# cw312_xc7a35t_fpga_pwr.net
KiCad netlist of a schematic drawn in Altium Designer
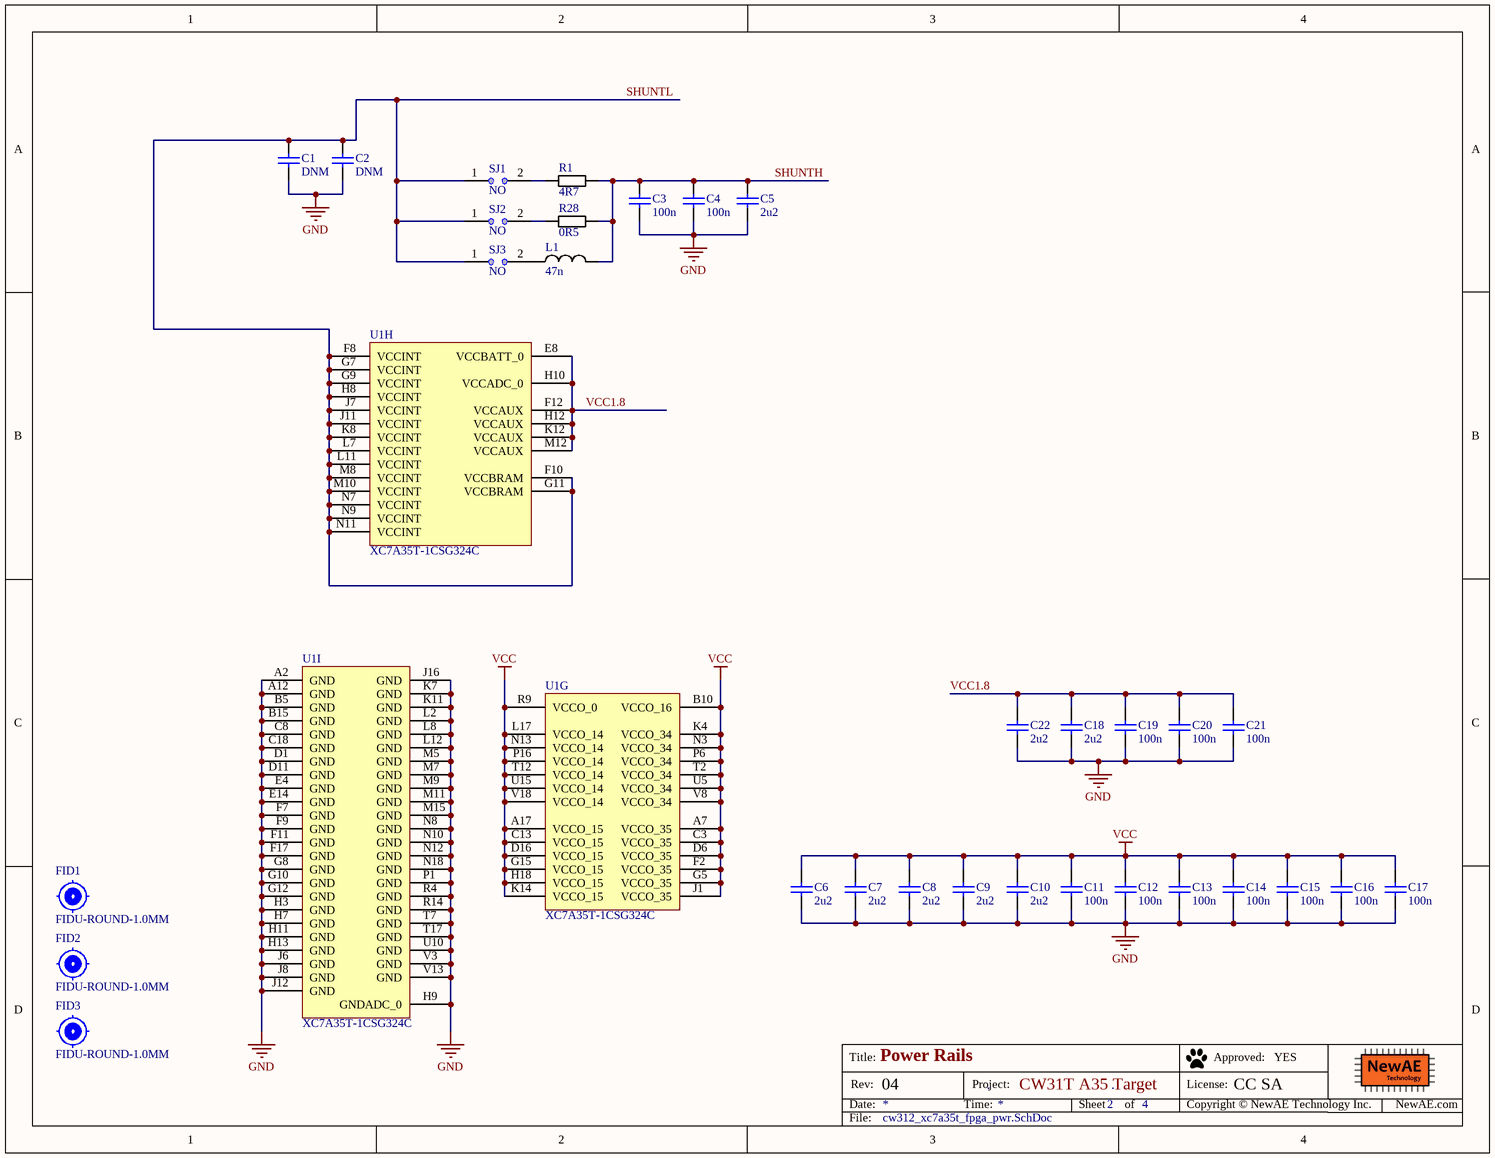
[diagram p0: cw312_xc7a35t_fpga_pwr.SchDoc]

(export (version "E")
  (design (tool "Eeschema 10.0.6"))
  (components
    (comp (ref "C1")
      (value "DNM")
      (footprint "CAPC0603_M")
      (fields (field (name "PART NUMBER") "CCHIP-100n-0603"))
      (libsource (lib "NewAE_AltiumLib") (part "CAP"))
    )
    (comp (ref "C2")
      (value "DNM")
      (footprint "CAPC0603_M")
      (fields (field (name "PART NUMBER") "CCHIP-100n-0603"))
      (libsource (lib "NewAE_AltiumLib") (part "CAP"))
    )
    (comp (ref "C3")
      (value "100n")
      (footprint "CAPC0603_M")
      (description "100n, 0603")
      (fields (field (name "PART NUMBER") "CCHIP-100n-0603"))
      (libsource (lib "NewAE_AltiumLib") (part "CAP"))
    )
    (comp (ref "C4")
      (value "100n")
      (footprint "CAPC0603_M")
      (description "100n, 0603")
      (fields (field (name "PART NUMBER") "CCHIP-100n-0603"))
      (libsource (lib "NewAE_AltiumLib") (part "CAP"))
    )
    (comp (ref "C5")
      (value "2u2")
      (footprint "CAPC0603_M")
      (description "2u2, 0603")
      (fields (field (name "PART NUMBER") "CCHIP-2u2-0603"))
      (libsource (lib "NewAE_AltiumLib") (part "CAP"))
    )
    (comp (ref "C6")
      (value "2u2")
      (footprint "CAPC0603_M")
      (description "2u2, 0603")
      (fields (field (name "PART NUMBER") "CCHIP-2u2-0603"))
      (libsource (lib "NewAE_AltiumLib") (part "CAP"))
    )
    (comp (ref "C7")
      (value "2u2")
      (footprint "CAPC0603_M")
      (description "2u2, 0603")
      (fields (field (name "PART NUMBER") "CCHIP-2u2-0603"))
      (libsource (lib "NewAE_AltiumLib") (part "CAP"))
    )
    (comp (ref "C8")
      (value "2u2")
      (footprint "CAPC0603_M")
      (description "2u2, 0603")
      (fields (field (name "PART NUMBER") "CCHIP-2u2-0603"))
      (libsource (lib "NewAE_AltiumLib") (part "CAP"))
    )
    (comp (ref "C9")
      (value "2u2")
      (footprint "CAPC0603_M")
      (description "2u2, 0603")
      (fields (field (name "PART NUMBER") "CCHIP-2u2-0603"))
      (libsource (lib "NewAE_AltiumLib") (part "CAP"))
    )
    (comp (ref "C10")
      (value "2u2")
      (footprint "CAPC0603_M")
      (description "2u2, 0603")
      (fields (field (name "PART NUMBER") "CCHIP-2u2-0603"))
      (libsource (lib "NewAE_AltiumLib") (part "CAP"))
    )
    (comp (ref "C11")
      (value "100n")
      (footprint "CAPC0402_M")
      (description "100n, 0402")
      (fields (field (name "PART NUMBER") "CCHIP-100n-0402"))
      (libsource (lib "NewAE_AltiumLib") (part "CAP"))
    )
    (comp (ref "C12")
      (value "100n")
      (footprint "CAPC0402_M")
      (description "100n, 0402")
      (fields (field (name "PART NUMBER") "CCHIP-100n-0402"))
      (libsource (lib "NewAE_AltiumLib") (part "CAP"))
    )
    (comp (ref "C13")
      (value "100n")
      (footprint "CAPC0402_M")
      (description "100n, 0402")
      (fields (field (name "PART NUMBER") "CCHIP-100n-0402"))
      (libsource (lib "NewAE_AltiumLib") (part "CAP"))
    )
    (comp (ref "C14")
      (value "100n")
      (footprint "CAPC0402_M")
      (description "100n, 0402")
      (fields (field (name "PART NUMBER") "CCHIP-100n-0402"))
      (libsource (lib "NewAE_AltiumLib") (part "CAP"))
    )
    (comp (ref "C15")
      (value "100n")
      (footprint "CAPC0402_M")
      (description "100n, 0402")
      (fields (field (name "PART NUMBER") "CCHIP-100n-0402"))
      (libsource (lib "NewAE_AltiumLib") (part "CAP"))
    )
    (comp (ref "C16")
      (value "100n")
      (footprint "CAPC0402_M")
      (description "100n, 0402")
      (fields (field (name "PART NUMBER") "CCHIP-100n-0402"))
      (libsource (lib "NewAE_AltiumLib") (part "CAP"))
    )
    (comp (ref "C17")
      (value "100n")
      (footprint "CAPC0402_M")
      (description "100n, 0402")
      (fields (field (name "PART NUMBER") "CCHIP-100n-0402"))
      (libsource (lib "NewAE_AltiumLib") (part "CAP"))
    )
    (comp (ref "C18")
      (value "2u2")
      (footprint "CAPC0603_M")
      (description "2u2, 0603")
      (fields (field (name "PART NUMBER") "CCHIP-2u2-0603"))
      (libsource (lib "NewAE_AltiumLib") (part "CAP"))
    )
    (comp (ref "C19")
      (value "100n")
      (footprint "CAPC0402_M")
      (description "100n, 0402")
      (fields (field (name "PART NUMBER") "CCHIP-100n-0402"))
      (libsource (lib "NewAE_AltiumLib") (part "CAP"))
    )
    (comp (ref "C20")
      (value "100n")
      (footprint "CAPC0402_M")
      (description "100n, 0402")
      (fields (field (name "PART NUMBER") "CCHIP-100n-0402"))
      (libsource (lib "NewAE_AltiumLib") (part "CAP"))
    )
    (comp (ref "C21")
      (value "100n")
      (footprint "CAPC0402_M")
      (description "100n, 0402")
      (fields (field (name "PART NUMBER") "CCHIP-100n-0402"))
      (libsource (lib "NewAE_AltiumLib") (part "CAP"))
    )
    (comp (ref "C22")
      (value "2u2")
      (footprint "CAPC0603_M")
      (description "2u2, 0603")
      (fields (field (name "PART NUMBER") "CCHIP-2u2-0603"))
      (libsource (lib "NewAE_AltiumLib") (part "CAP"))
    )
    (comp (ref "FID1")
      (value "FIDU-ROUND-1.0MM")
      (footprint "FIDU-ROUND-1.0mm")
      (description "ROUND FIDUCIAL")
      (libsource (lib "NewAE_AltiumLib") (part "FIDU-ROUND-1.0MM"))
    )
    (comp (ref "FID2")
      (value "FIDU-ROUND-1.0MM")
      (footprint "FIDU-ROUND-1.0mm")
      (description "ROUND FIDUCIAL")
      (libsource (lib "NewAE_AltiumLib") (part "FIDU-ROUND-1.0MM"))
    )
    (comp (ref "FID3")
      (value "FIDU-ROUND-1.0MM")
      (footprint "FIDU-ROUND-1.0mm")
      (description "ROUND FIDUCIAL")
      (libsource (lib "NewAE_AltiumLib") (part "FIDU-ROUND-1.0MM"))
    )
    (comp (ref "L1")
      (value "47n")
      (footprint "IND_0603")
      (description "FIXED IND 47NH 380MA 290 MOHM")
      (fields (field (name "PART NUMBER") "LCHIP-47N-0603") (field (name "TOLERANCE") "±5%"))
      (libsource (lib "NewAE_AltiumLib") (part "IND"))
    )
    (comp (ref "R1")
      (value "4R7")
      (footprint "RESC1608X55N")
      (description "4R7 res, 0603, 1%, 1/10W")
      (fields (field (name "PART NUMBER") "RCHIP-4R7-0603") (field (name "TOLERANCE") "1%"))
      (libsource (lib "NewAE_AltiumLib") (part "RES-EU"))
    )
    (comp (ref "R28")
      (value "0R5")
      (footprint "RESC1608X55N")
      (description "0R500 res, 0603, 1%, 1/10W")
      (fields (field (name "PART NUMBER") "RCHIP-0R500-0603") (field (name "TOLERANCE") "1%"))
      (libsource (lib "NewAE_AltiumLib") (part "RES-EU"))
    )
    (comp (ref "SJ1")
      (value "NO")
      (footprint "SJ_2S_NO")
      (description "Solder Jumper, NO")
      (fields (field (name "PART NUMBER") "SJ_2S_NO"))
      (libsource (lib "NewAE_AltiumLib") (part "SJ_2S_NO"))
    )
    (comp (ref "SJ2")
      (value "NO")
      (footprint "SJ_2S_NO")
      (description "Solder Jumper, NO")
      (fields (field (name "PART NUMBER") "SJ_2S_NO"))
      (libsource (lib "NewAE_AltiumLib") (part "SJ_2S_NO"))
    )
    (comp (ref "SJ3")
      (value "NO")
      (footprint "SJ_2S_NO")
      (description "Solder Jumper, NO")
      (fields (field (name "PART NUMBER") "SJ_2S_NO"))
      (libsource (lib "NewAE_AltiumLib") (part "SJ_2S_NO"))
    )
    (comp (ref "U1")
      (value "XC7A35T-1CSG324C")
      (footprint "CSG324")
      (description "Artix-7 FPGA, 210 User I/Os, 0 GTP, 324-Ball BGA, Speed Grade 1, Commercial Grade, Pb-Free")
      (fields (field (name "MANUFACTURER") "Xilinx"))
      (libsource (lib "Altium Content Vault") (part "XLNX-XC7A35T-CSG324"))
    )
  )
  (nets
    (net (code "1") (name "/SHUNTH") (class "Default")
      (node (ref "C3") (pin "1") (pinfunction "1_1") (pintype "passive"))
      (node (ref "C4") (pin "1") (pinfunction "1_1") (pintype "passive"))
      (node (ref "C5") (pin "1") (pinfunction "1_1") (pintype "passive"))
      (node (ref "L1") (pin "2") (pinfunction "2_2") (pintype "passive"))
      (node (ref "R1") (pin "2") (pinfunction "2_2") (pintype "passive"))
      (node (ref "R28") (pin "2") (pinfunction "2_2") (pintype "passive"))
    )
    (net (code "2") (name "/SHUNTL") (class "Default")
      (node (ref "C1") (pin "1") (pinfunction "1_1") (pintype "passive"))
      (node (ref "C2") (pin "1") (pinfunction "1_1") (pintype "passive"))
      (node (ref "SJ1") (pin "1") (pinfunction "1_1") (pintype "passive"))
      (node (ref "SJ2") (pin "1") (pinfunction "1_1") (pintype "passive"))
      (node (ref "SJ3") (pin "1") (pinfunction "1_1") (pintype "passive"))
      (node (ref "U1") (pin "F10") (pinfunction "VCCBRAM_F10") (pintype "power_in"))
      (node (ref "U1") (pin "F8") (pinfunction "VCCINT_F8") (pintype "power_in"))
      (node (ref "U1") (pin "G11") (pinfunction "VCCBRAM_G11") (pintype "power_in"))
      (node (ref "U1") (pin "G7") (pinfunction "VCCINT_G7") (pintype "power_in"))
      (node (ref "U1") (pin "G9") (pinfunction "VCCINT_G9") (pintype "power_in"))
      (node (ref "U1") (pin "H8") (pinfunction "VCCINT_H8") (pintype "power_in"))
      (node (ref "U1") (pin "J11") (pinfunction "VCCINT_J11") (pintype "power_in"))
      (node (ref "U1") (pin "J7") (pinfunction "VCCINT_J7") (pintype "power_in"))
      (node (ref "U1") (pin "K8") (pinfunction "VCCINT_K8") (pintype "power_in"))
      (node (ref "U1") (pin "L11") (pinfunction "VCCINT_L11") (pintype "power_in"))
      (node (ref "U1") (pin "L7") (pinfunction "VCCINT_L7") (pintype "power_in"))
      (node (ref "U1") (pin "M10") (pinfunction "VCCINT_M10") (pintype "power_in"))
      (node (ref "U1") (pin "M8") (pinfunction "VCCINT_M8") (pintype "power_in"))
      (node (ref "U1") (pin "N11") (pinfunction "VCCINT_N11") (pintype "power_in"))
      (node (ref "U1") (pin "N7") (pinfunction "VCCINT_N7") (pintype "power_in"))
      (node (ref "U1") (pin "N9") (pinfunction "VCCINT_N9") (pintype "power_in"))
    )
    (net (code "3") (name "/VCC1.8") (class "Default")
      (node (ref "C18") (pin "1") (pinfunction "1_1") (pintype "passive"))
      (node (ref "C19") (pin "1") (pinfunction "1_1") (pintype "passive"))
      (node (ref "C20") (pin "1") (pinfunction "1_1") (pintype "passive"))
      (node (ref "C21") (pin "1") (pinfunction "1_1") (pintype "passive"))
      (node (ref "C22") (pin "1") (pinfunction "1_1") (pintype "passive"))
      (node (ref "U1") (pin "E8") (pinfunction "VCCBATT_0_E8") (pintype "power_in"))
      (node (ref "U1") (pin "F12") (pinfunction "VCCAUX_F12") (pintype "power_in"))
      (node (ref "U1") (pin "H10") (pinfunction "VCCADC_0_H10") (pintype "power_in"))
      (node (ref "U1") (pin "H12") (pinfunction "VCCAUX_H12") (pintype "power_in"))
      (node (ref "U1") (pin "K12") (pinfunction "VCCAUX_K12") (pintype "power_in"))
      (node (ref "U1") (pin "M12") (pinfunction "VCCAUX_M12") (pintype "power_in"))
    )
    (net (code "4") (name "GND") (class "Default")
      (node (ref "C1") (pin "2") (pinfunction "2_2") (pintype "passive"))
      (node (ref "C10") (pin "2") (pinfunction "2_2") (pintype "passive"))
      (node (ref "C11") (pin "2") (pinfunction "2_2") (pintype "passive"))
      (node (ref "C12") (pin "2") (pinfunction "2_2") (pintype "passive"))
      (node (ref "C13") (pin "2") (pinfunction "2_2") (pintype "passive"))
      (node (ref "C14") (pin "2") (pinfunction "2_2") (pintype "passive"))
      (node (ref "C15") (pin "2") (pinfunction "2_2") (pintype "passive"))
      (node (ref "C16") (pin "2") (pinfunction "2_2") (pintype "passive"))
      (node (ref "C17") (pin "2") (pinfunction "2_2") (pintype "passive"))
      (node (ref "C18") (pin "2") (pinfunction "2_2") (pintype "passive"))
      (node (ref "C19") (pin "2") (pinfunction "2_2") (pintype "passive"))
      (node (ref "C2") (pin "2") (pinfunction "2_2") (pintype "passive"))
      (node (ref "C20") (pin "2") (pinfunction "2_2") (pintype "passive"))
      (node (ref "C21") (pin "2") (pinfunction "2_2") (pintype "passive"))
      (node (ref "C22") (pin "2") (pinfunction "2_2") (pintype "passive"))
      (node (ref "C3") (pin "2") (pinfunction "2_2") (pintype "passive"))
      (node (ref "C4") (pin "2") (pinfunction "2_2") (pintype "passive"))
      (node (ref "C5") (pin "2") (pinfunction "2_2") (pintype "passive"))
      (node (ref "C6") (pin "2") (pinfunction "2_2") (pintype "passive"))
      (node (ref "C7") (pin "2") (pinfunction "2_2") (pintype "passive"))
      (node (ref "C8") (pin "2") (pinfunction "2_2") (pintype "passive"))
      (node (ref "C9") (pin "2") (pinfunction "2_2") (pintype "passive"))
      (node (ref "U1") (pin "A12") (pinfunction "GND_A12") (pintype "power_in"))
      (node (ref "U1") (pin "A2") (pinfunction "GND_A2") (pintype "power_in"))
      (node (ref "U1") (pin "B15") (pinfunction "GND_B15") (pintype "power_in"))
      (node (ref "U1") (pin "B5") (pinfunction "GND_B5") (pintype "power_in"))
      (node (ref "U1") (pin "C18") (pinfunction "GND_C18") (pintype "power_in"))
      (node (ref "U1") (pin "C8") (pinfunction "GND_C8") (pintype "power_in"))
      (node (ref "U1") (pin "D1") (pinfunction "GND_D1") (pintype "power_in"))
      (node (ref "U1") (pin "D11") (pinfunction "GND_D11") (pintype "power_in"))
      (node (ref "U1") (pin "E14") (pinfunction "GND_E14") (pintype "power_in"))
      (node (ref "U1") (pin "E4") (pinfunction "GND_E4") (pintype "power_in"))
      (node (ref "U1") (pin "F11") (pinfunction "GND_F11") (pintype "power_in"))
      (node (ref "U1") (pin "F17") (pinfunction "GND_F17") (pintype "power_in"))
      (node (ref "U1") (pin "F7") (pinfunction "GND_F7") (pintype "power_in"))
      (node (ref "U1") (pin "F9") (pinfunction "GND_F9") (pintype "power_in"))
      (node (ref "U1") (pin "G10") (pinfunction "GND_G10") (pintype "power_in"))
      (node (ref "U1") (pin "G12") (pinfunction "GND_G12") (pintype "power_in"))
      (node (ref "U1") (pin "G8") (pinfunction "GND_G8") (pintype "power_in"))
      (node (ref "U1") (pin "H11") (pinfunction "GND_H11") (pintype "power_in"))
      (node (ref "U1") (pin "H13") (pinfunction "GND_H13") (pintype "power_in"))
      (node (ref "U1") (pin "H3") (pinfunction "GND_H3") (pintype "power_in"))
      (node (ref "U1") (pin "H7") (pinfunction "GND_H7") (pintype "power_in"))
      (node (ref "U1") (pin "H9") (pinfunction "GNDADC_0_H9") (pintype "power_in"))
      (node (ref "U1") (pin "J12") (pinfunction "GND_J12") (pintype "power_in"))
      (node (ref "U1") (pin "J16") (pinfunction "GND_J16") (pintype "power_in"))
      (node (ref "U1") (pin "J6") (pinfunction "GND_J6") (pintype "power_in"))
      (node (ref "U1") (pin "J8") (pinfunction "GND_J8") (pintype "power_in"))
      (node (ref "U1") (pin "K11") (pinfunction "GND_K11") (pintype "power_in"))
      (node (ref "U1") (pin "K7") (pinfunction "GND_K7") (pintype "power_in"))
      (node (ref "U1") (pin "L12") (pinfunction "GND_L12") (pintype "power_in"))
      (node (ref "U1") (pin "L2") (pinfunction "GND_L2") (pintype "power_in"))
      (node (ref "U1") (pin "L8") (pinfunction "GND_L8") (pintype "power_in"))
      (node (ref "U1") (pin "M11") (pinfunction "GND_M11") (pintype "power_in"))
      (node (ref "U1") (pin "M15") (pinfunction "GND_M15") (pintype "power_in"))
      (node (ref "U1") (pin "M5") (pinfunction "GND_M5") (pintype "power_in"))
      (node (ref "U1") (pin "M7") (pinfunction "GND_M7") (pintype "power_in"))
      (node (ref "U1") (pin "M9") (pinfunction "GND_M9") (pintype "power_in"))
      (node (ref "U1") (pin "N10") (pinfunction "GND_N10") (pintype "power_in"))
      (node (ref "U1") (pin "N12") (pinfunction "GND_N12") (pintype "power_in"))
      (node (ref "U1") (pin "N18") (pinfunction "GND_N18") (pintype "power_in"))
      (node (ref "U1") (pin "N8") (pinfunction "GND_N8") (pintype "power_in"))
      (node (ref "U1") (pin "P1") (pinfunction "GND_P1") (pintype "power_in"))
      (node (ref "U1") (pin "R14") (pinfunction "GND_R14") (pintype "power_in"))
      (node (ref "U1") (pin "R4") (pinfunction "GND_R4") (pintype "power_in"))
      (node (ref "U1") (pin "T17") (pinfunction "GND_T17") (pintype "power_in"))
      (node (ref "U1") (pin "T7") (pinfunction "GND_T7") (pintype "power_in"))
      (node (ref "U1") (pin "U10") (pinfunction "GND_U10") (pintype "power_in"))
      (node (ref "U1") (pin "V13") (pinfunction "GND_V13") (pintype "power_in"))
      (node (ref "U1") (pin "V3") (pinfunction "GND_V3") (pintype "power_in"))
    )
    (net (code "5") (name "Net-(L1-Pad1)") (class "Default")
      (node (ref "L1") (pin "1") (pinfunction "1_1") (pintype "passive"))
      (node (ref "SJ3") (pin "2") (pinfunction "2_2") (pintype "passive"))
    )
    (net (code "6") (name "Net-(R1-Pad1)") (class "Default")
      (node (ref "R1") (pin "1") (pinfunction "1_1") (pintype "passive"))
      (node (ref "SJ1") (pin "2") (pinfunction "2_2") (pintype "passive"))
    )
    (net (code "7") (name "Net-(R28-Pad1)") (class "Default")
      (node (ref "R28") (pin "1") (pinfunction "1_1") (pintype "passive"))
      (node (ref "SJ2") (pin "2") (pinfunction "2_2") (pintype "passive"))
    )
    (net (code "8") (name "VCC") (class "Default")
      (node (ref "C10") (pin "1") (pinfunction "1_1") (pintype "passive"))
      (node (ref "C11") (pin "1") (pinfunction "1_1") (pintype "passive"))
      (node (ref "C12") (pin "1") (pinfunction "1_1") (pintype "passive"))
      (node (ref "C13") (pin "1") (pinfunction "1_1") (pintype "passive"))
      (node (ref "C14") (pin "1") (pinfunction "1_1") (pintype "passive"))
      (node (ref "C15") (pin "1") (pinfunction "1_1") (pintype "passive"))
      (node (ref "C16") (pin "1") (pinfunction "1_1") (pintype "passive"))
      (node (ref "C17") (pin "1") (pinfunction "1_1") (pintype "passive"))
      (node (ref "C6") (pin "1") (pinfunction "1_1") (pintype "passive"))
      (node (ref "C7") (pin "1") (pinfunction "1_1") (pintype "passive"))
      (node (ref "C8") (pin "1") (pinfunction "1_1") (pintype "passive"))
      (node (ref "C9") (pin "1") (pinfunction "1_1") (pintype "passive"))
      (node (ref "U1") (pin "A17") (pinfunction "VCCO_15_A17") (pintype "power_in"))
      (node (ref "U1") (pin "A7") (pinfunction "VCCO_35_A7") (pintype "power_in"))
      (node (ref "U1") (pin "B10") (pinfunction "VCCO_16_B10") (pintype "power_in"))
      (node (ref "U1") (pin "C13") (pinfunction "VCCO_15_C13") (pintype "power_in"))
      (node (ref "U1") (pin "C3") (pinfunction "VCCO_35_C3") (pintype "power_in"))
      (node (ref "U1") (pin "D16") (pinfunction "VCCO_15_D16") (pintype "power_in"))
      (node (ref "U1") (pin "D6") (pinfunction "VCCO_35_D6") (pintype "power_in"))
      (node (ref "U1") (pin "F2") (pinfunction "VCCO_35_F2") (pintype "power_in"))
      (node (ref "U1") (pin "G15") (pinfunction "VCCO_15_G15") (pintype "power_in"))
      (node (ref "U1") (pin "G5") (pinfunction "VCCO_35_G5") (pintype "power_in"))
      (node (ref "U1") (pin "H18") (pinfunction "VCCO_15_H18") (pintype "power_in"))
      (node (ref "U1") (pin "J1") (pinfunction "VCCO_35_J1") (pintype "power_in"))
      (node (ref "U1") (pin "K14") (pinfunction "VCCO_15_K14") (pintype "power_in"))
      (node (ref "U1") (pin "K4") (pinfunction "VCCO_34_K4") (pintype "power_in"))
      (node (ref "U1") (pin "L17") (pinfunction "VCCO_14_L17") (pintype "power_in"))
      (node (ref "U1") (pin "N13") (pinfunction "VCCO_14_N13") (pintype "power_in"))
      (node (ref "U1") (pin "N3") (pinfunction "VCCO_34_N3") (pintype "power_in"))
      (node (ref "U1") (pin "P16") (pinfunction "VCCO_14_P16") (pintype "power_in"))
      (node (ref "U1") (pin "P6") (pinfunction "VCCO_34_P6") (pintype "power_in"))
      (node (ref "U1") (pin "R9") (pinfunction "VCCO_0_R9") (pintype "power_in"))
      (node (ref "U1") (pin "T12") (pinfunction "VCCO_14_T12") (pintype "power_in"))
      (node (ref "U1") (pin "T2") (pinfunction "VCCO_34_T2") (pintype "power_in"))
      (node (ref "U1") (pin "U15") (pinfunction "VCCO_14_U15") (pintype "power_in"))
      (node (ref "U1") (pin "U5") (pinfunction "VCCO_34_U5") (pintype "power_in"))
      (node (ref "U1") (pin "V18") (pinfunction "VCCO_14_V18") (pintype "power_in"))
      (node (ref "U1") (pin "V8") (pinfunction "VCCO_34_V8") (pintype "power_in"))
    )
  )
)
